# USB-C.net
KiCad netlist of a schematic drawn in Altium Designer
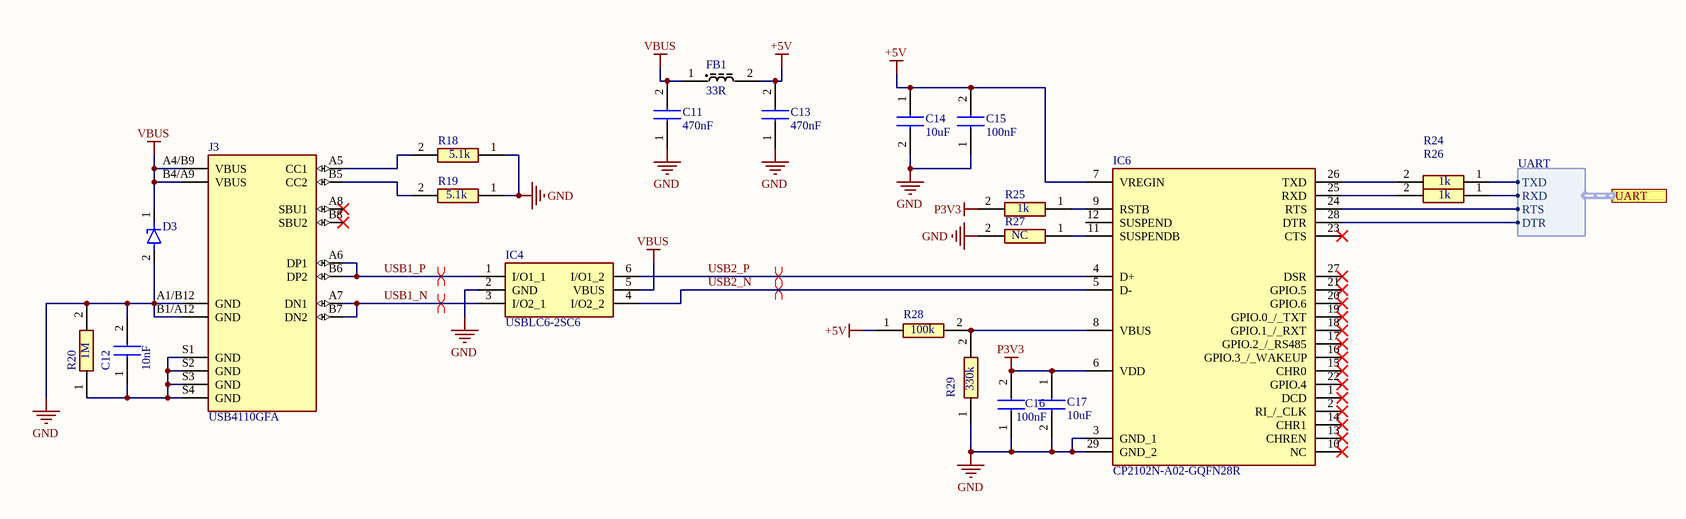
[diagram p0: USB-C.SchDoc]

(export (version "E")
  (design (tool "Eeschema 10.0.6"))
  (components
    (comp (ref "C11")
      (value "470nF")
      (footprint "SamacSys:GRM15x")
      (description "Capacitor")
      (fields
        (field (name "MANUFACTURER_PART_NUMBER") "GRM155R61H474KE11J")
        (field (name "MOUSER PART NUMBER") "81-GRM155R61H474KE1J")
      )
      (libsource (lib "*") (part "GRM155R61H474KE11J"))
    )
    (comp (ref "C12")
      (value "10nF")
      (footprint "SamacSys:GRM15x")
      (description "Capacitor")
      (fields
        (field (name "MANUFACTURER_PART_NUMBER") "GRM155R71H103KA88D")
        (field (name "MOUSER PART NUMBER") "81-GRM155R71H103KA8D")
      )
      (libsource (lib "SamacSys") (part "GRM155R71H103KA88D"))
    )
    (comp (ref "C13")
      (value "470nF")
      (footprint "SamacSys:GRM15x")
      (description "Capacitor")
      (fields
        (field (name "MANUFACTURER_PART_NUMBER") "GRM155R61H474KE11J")
        (field (name "MOUSER PART NUMBER") "81-GRM155R61H474KE1J")
      )
      (libsource (lib "*") (part "GRM155R61H474KE11J"))
    )
    (comp (ref "C14")
      (value "10uF")
      (footprint "SamacSys:GRM18x")
      (description "Capacitor")
      (fields
        (field (name "MANUFACTURER_PART_NUMBER") "GRM188R61E106KA73D")
        (field (name "MOUSER PART NUMBER") "81-GRM188R61E106KA3D")
      )
      (libsource (lib "*") (part "GRM188R61E106KA73D"))
    )
    (comp (ref "C15")
      (value "100nF")
      (footprint "SamacSys:CAPC1005X70N")
      (description "Capacitor")
      (fields
        (field (name "MANUFACTURER_PART_NUMBER") "GRM155R61A104KA01D")
        (field (name "MOUSER PART NUMBER") "81-GRM155R61A104KA01")
      )
      (libsource (lib "*") (part "GRM155R61A104KA01D"))
    )
    (comp (ref "C16")
      (value "100nF")
      (footprint "SamacSys:CAPC1005X70N")
      (description "Capacitor")
      (fields
        (field (name "MANUFACTURER_PART_NUMBER") "GRM155R61A104KA01D")
        (field (name "MOUSER PART NUMBER") "81-GRM155R61A104KA01")
      )
      (libsource (lib "*") (part "GRM155R61A104KA01D"))
    )
    (comp (ref "C17")
      (value "10uF")
      (footprint "SamacSys:GRM18x")
      (description "Capacitor")
      (fields
        (field (name "MANUFACTURER_PART_NUMBER") "GRM188R61E106KA73D")
        (field (name "MOUSER PART NUMBER") "81-GRM188R61E106KA3D")
      )
      (libsource (lib "*") (part "GRM188R61E106KA73D"))
    )
    (comp (ref "D3")
      (value "ESDA25P35-1U1M")
      (footprint "SamacSys:ESDA25P351U1M")
      (description "TVS Diode (Uni-directional)")
      (fields (field (name "MOUSER PART NUMBER") "511-ESDA25P35-1U1M"))
      (libsource (lib "SamacSys") (part "ESDA25P35-1U1M"))
    )
    (comp (ref "FB1")
      (value "33R")
      (footprint "SamacSys:BLM18SP221SN1B")
      (description "Ferrite Bead")
      (fields
        (field (name "MANUFACTURER_PART_NUMBER") "BLM18SG330SN1D")
        (field (name "MOUSER PART NUMBER") "81-BLM18SG330SN1D")
      )
      (libsource (lib "SamacSys") (part "BLM18SG330SN1D"))
    )
    (comp (ref "IC4")
      (value "USBLC6-2SC6")
      (footprint "SamacSys:SOT95P280X145-6N")
      (description "Integrated Circuit")
      (fields (field (name "MOUSER PART NUMBER") "511-USBLC6-2SC6"))
      (libsource (lib "SamacSys") (part "USBLC6-2SC6"))
    )
    (comp (ref "IC6")
      (value "CP2102N-A02-GQFN28R")
      (footprint "SamacSys:QFN50P500X500X80-29N-D")
      (description "Integrated Circuit")
      (fields (field (name "MOUSER PART NUMBER") "634-CP2102NA02QFN28R"))
      (libsource (lib "SamacSys") (part "CP2102N-A02-GQFN28R"))
    )
    (comp (ref "J3")
      (value "USB4110GFA")
      (footprint "SamacSys:GCT_USB4110GFA")
      (fields (field (name "MF") "Global Connector Technology"))
      (libsource (lib "SamacSys") (part "USB4110GFA"))
    )
    (comp (ref "R18")
      (value "5.1k")
      (footprint "SamacSys:RESC1005X35N")
      (description "Resistor")
      (fields (field (name "MANUFACTURER_PART_NUMBER") "RT0402FRE075K1L"))
      (libsource (lib "SamacSys") (part "RT0402FRE075K1L"))
    )
    (comp (ref "R19")
      (value "5.1k")
      (footprint "SamacSys:RESC1005X35N")
      (description "Resistor")
      (fields (field (name "MANUFACTURER_PART_NUMBER") "RT0402FRE075K1L"))
      (libsource (lib "SamacSys") (part "RT0402FRE075K1L"))
    )
    (comp (ref "R20")
      (value "1M")
      (footprint "SamacSys:RESC1005X40N")
      (description "Resistor")
      (fields
        (field (name "MANUFACTURER_PART_NUMBER") "RC0402FR-071ML")
        (field (name "MOUSER PART NUMBER") "603-RC0402FR-071ML")
      )
      (libsource (lib "*") (part "RC0402FR-071ML"))
    )
    (comp (ref "R24")
      (value "1k")
      (footprint "SamacSys:RESC1005X35N")
      (description "Resistor")
      (fields
        (field (name "MANUFACTURER_PART_NUMBER") "RT0402FRE071KL")
        (field (name "ARROW PART NUMBER") "RT0402FRE07100KL")
      )
      (libsource (lib "SamacSys") (part "RT0402FRE071KL"))
    )
    (comp (ref "R25")
      (value "1k")
      (footprint "SamacSys:RESC1005X35N")
      (description "Resistor")
      (fields
        (field (name "MANUFACTURER_PART_NUMBER") "RT0402FRE071KL")
        (field (name "ARROW PART NUMBER") "RT0402FRE07100KL")
      )
      (libsource (lib "SamacSys") (part "RT0402FRE071KL"))
    )
    (comp (ref "R26")
      (value "1k")
      (footprint "SamacSys:RESC1005X35N")
      (description "Resistor")
      (fields
        (field (name "MANUFACTURER_PART_NUMBER") "RT0402FRE071KL")
        (field (name "ARROW PART NUMBER") "RT0402FRE07100KL")
      )
      (libsource (lib "SamacSys") (part "RT0402FRE071KL"))
    )
    (comp (ref "R27")
      (value "NC")
      (footprint "SamacSys:RESC1005X35N")
      (description "Resistor")
      (fields
        (field (name "MANUFACTURER_PART_NUMBER") "RT0402FRE0710KL")
        (field (name "MOUSER PART NUMBER") "603-RT0402FRE0710KL")
      )
      (libsource (lib "SamacSys") (part "RT0402FRE0710KL"))
    )
    (comp (ref "R28")
      (value "100k")
      (footprint "SamacSys:RESC1005X40N")
      (description "Resistor")
      (fields (field (name "MANUFACTURER_PART_NUMBER") "RC0402BR-07100KL"))
      (libsource (lib "SamacSys") (part "RC0402BR-07100KL"))
    )
    (comp (ref "R29")
      (value "330k")
      (footprint "SamacSys:RESC1005X40N")
      (description "Resistor")
      (fields (field (name "MANUFACTURER_PART_NUMBER") "RC0402BR-07330KL"))
      (libsource (lib "SamacSys") (part "RC0402BR-07330KL"))
    )
  )
  (nets
    (net (code "2") (name "+5V") (class "Default")
      (node (ref "C13") (pin "2") (pinfunction "2_2") (pintype "passive"))
      (node (ref "C14") (pin "1") (pinfunction "1_1") (pintype "passive"))
      (node (ref "C15") (pin "2") (pinfunction "2_2") (pintype "passive"))
      (node (ref "FB1") (pin "2") (pinfunction "2_2") (pintype "passive"))
      (node (ref "IC6") (pin "7") (pinfunction "VREGIN_7") (pintype "passive"))
      (node (ref "R28") (pin "1") (pinfunction "1_1") (pintype "passive"))
    )
    (net (code "3") (name "/DTR") (class "Default")
      (node (ref "IC6") (pin "28") (pinfunction "DTR_28") (pintype "passive"))
    )
    (net (code "4") (name "/RTS") (class "Default")
      (node (ref "IC6") (pin "24") (pinfunction "RTS_24") (pintype "passive"))
    )
    (net (code "5") (name "/RXD") (class "Default")
      (node (ref "R26") (pin "1") (pinfunction "1_1") (pintype "passive"))
    )
    (net (code "6") (name "/TXD") (class "Default")
      (node (ref "R24") (pin "1") (pinfunction "1_1") (pintype "passive"))
    )
    (net (code "7") (name "/USB1_N") (class "Default")
      (node (ref "IC4") (pin "3") (pinfunction "I/O2_1_3") (pintype "passive"))
      (node (ref "J3") (pin "A7") (pinfunction "DN1_A7") (pintype "bidirectional"))
      (node (ref "J3") (pin "B7") (pinfunction "DN2_B7") (pintype "bidirectional"))
    )
    (net (code "8") (name "/USB1_P") (class "Default")
      (node (ref "IC4") (pin "1") (pinfunction "I/O1_1_1") (pintype "passive"))
      (node (ref "J3") (pin "A6") (pinfunction "DP1_A6") (pintype "bidirectional"))
      (node (ref "J3") (pin "B6") (pinfunction "DP2_B6") (pintype "bidirectional"))
    )
    (net (code "9") (name "/USB2_N") (class "Default")
      (node (ref "IC4") (pin "4") (pinfunction "I/O2_2_4") (pintype "passive"))
      (node (ref "IC6") (pin "5") (pinfunction "D-_5") (pintype "passive"))
    )
    (net (code "10") (name "/USB2_P") (class "Default")
      (node (ref "IC4") (pin "6") (pinfunction "I/O1_2_6") (pintype "passive"))
      (node (ref "IC6") (pin "4") (pinfunction "D+_4") (pintype "passive"))
    )
    (net (code "12") (name "GND") (class "Default")
      (node (ref "C11") (pin "1") (pinfunction "1_1") (pintype "passive"))
      (node (ref "C12") (pin "2") (pinfunction "2_2") (pintype "passive"))
      (node (ref "C13") (pin "1") (pinfunction "1_1") (pintype "passive"))
      (node (ref "C14") (pin "2") (pinfunction "2_2") (pintype "passive"))
      (node (ref "C15") (pin "1") (pinfunction "1_1") (pintype "passive"))
      (node (ref "C16") (pin "1") (pinfunction "1_1") (pintype "passive"))
      (node (ref "C17") (pin "2") (pinfunction "2_2") (pintype "passive"))
      (node (ref "D3") (pin "2") (pinfunction "A_2") (pintype "passive"))
      (node (ref "IC4") (pin "2") (pinfunction "GND_2") (pintype "passive"))
      (node (ref "IC6") (pin "29") (pinfunction "GND_2_29") (pintype "passive"))
      (node (ref "IC6") (pin "3") (pinfunction "GND_1_3") (pintype "passive"))
      (node (ref "J3") (pin "A1/B12") (pinfunction "GND_A1/B12") (pintype "power_in"))
      (node (ref "J3") (pin "B1/A12") (pinfunction "GND_B1/A12") (pintype "power_in"))
      (node (ref "R18") (pin "1") (pinfunction "1_1") (pintype "passive"))
      (node (ref "R19") (pin "1") (pinfunction "1_1") (pintype "passive"))
      (node (ref "R20") (pin "2") (pinfunction "2_2") (pintype "passive"))
      (node (ref "R27") (pin "2") (pinfunction "2_2") (pintype "passive"))
      (node (ref "R29") (pin "1") (pinfunction "1_1") (pintype "passive"))
    )
    (net (code "13") (name "Net-(C12-Pad1)") (class "Default")
      (node (ref "C12") (pin "1") (pinfunction "1_1") (pintype "passive"))
      (node (ref "J3") (pin "S1") (pinfunction "GND_S1") (pintype "power_in"))
      (node (ref "J3") (pin "S2") (pinfunction "GND_S2") (pintype "power_in"))
      (node (ref "J3") (pin "S3") (pinfunction "GND_S3") (pintype "power_in"))
      (node (ref "J3") (pin "S4") (pinfunction "GND_S4") (pintype "power_in"))
      (node (ref "R20") (pin "1") (pinfunction "1_1") (pintype "passive"))
    )
    (net (code "14") (name "Net-(IC6-RSTB)") (class "Default")
      (node (ref "IC6") (pin "9") (pinfunction "RSTB_9") (pintype "passive"))
      (node (ref "R25") (pin "1") (pinfunction "1_1") (pintype "passive"))
    )
    (net (code "15") (name "Net-(IC6-RXD)") (class "Default")
      (node (ref "IC6") (pin "25") (pinfunction "RXD_25") (pintype "passive"))
      (node (ref "R26") (pin "2") (pinfunction "2_2") (pintype "passive"))
    )
    (net (code "16") (name "Net-(IC6-SUSPENDB)") (class "Default")
      (node (ref "IC6") (pin "11") (pinfunction "SUSPENDB_11") (pintype "passive"))
      (node (ref "R27") (pin "1") (pinfunction "1_1") (pintype "passive"))
    )
    (net (code "17") (name "Net-(IC6-TXD)") (class "Default")
      (node (ref "IC6") (pin "26") (pinfunction "TXD_26") (pintype "passive"))
      (node (ref "R24") (pin "2") (pinfunction "2_2") (pintype "passive"))
    )
    (net (code "18") (name "Net-(IC6-VBUS)") (class "Default")
      (node (ref "IC6") (pin "8") (pinfunction "VBUS_8") (pintype "passive"))
      (node (ref "R28") (pin "2") (pinfunction "2_2") (pintype "passive"))
      (node (ref "R29") (pin "2") (pinfunction "2_2") (pintype "passive"))
    )
    (net (code "19") (name "Net-(J3-CC1)") (class "Default")
      (node (ref "J3") (pin "A5") (pinfunction "CC1_A5") (pintype "bidirectional"))
      (node (ref "R18") (pin "2") (pinfunction "2_2") (pintype "passive"))
    )
    (net (code "20") (name "Net-(J3-CC2)") (class "Default")
      (node (ref "J3") (pin "B5") (pinfunction "CC2_B5") (pintype "bidirectional"))
      (node (ref "R19") (pin "2") (pinfunction "2_2") (pintype "passive"))
    )
    (net (code "21") (name "P3V3") (class "Default")
      (node (ref "C16") (pin "2") (pinfunction "2_2") (pintype "passive"))
      (node (ref "C17") (pin "1") (pinfunction "1_1") (pintype "passive"))
      (node (ref "IC6") (pin "6") (pinfunction "VDD_6") (pintype "passive"))
      (node (ref "R25") (pin "2") (pinfunction "2_2") (pintype "passive"))
    )
    (net (code "22") (name "VBUS") (class "Default")
      (node (ref "C11") (pin "2") (pinfunction "2_2") (pintype "passive"))
      (node (ref "D3") (pin "1") (pinfunction "K_1") (pintype "passive"))
      (node (ref "FB1") (pin "1") (pinfunction "1_1") (pintype "passive"))
      (node (ref "IC4") (pin "5") (pinfunction "VBUS_5") (pintype "passive"))
      (node (ref "J3") (pin "A4/B9") (pinfunction "VBUS_A4/B9") (pintype "power_in"))
      (node (ref "J3") (pin "B4/A9") (pinfunction "VBUS_B4/A9") (pintype "power_in"))
    )
    (net (code "23") (name "unconnected-(IC6-CHR0-Pad15)") (class "Default")
      (node (ref "IC6") (pin "15") (pinfunction "CHR0_15") (pintype "passive+no_connect"))
    )
    (net (code "24") (name "unconnected-(IC6-CHR1-Pad14)") (class "Default")
      (node (ref "IC6") (pin "14") (pinfunction "CHR1_14") (pintype "passive+no_connect"))
    )
    (net (code "25") (name "unconnected-(IC6-CHREN-Pad13)") (class "Default")
      (node (ref "IC6") (pin "13") (pinfunction "CHREN_13") (pintype "passive+no_connect"))
    )
    (net (code "26") (name "unconnected-(IC6-CTS-Pad23)") (class "Default")
      (node (ref "IC6") (pin "23") (pinfunction "CTS_23") (pintype "passive+no_connect"))
    )
    (net (code "27") (name "unconnected-(IC6-DCD-Pad1)") (class "Default")
      (node (ref "IC6") (pin "1") (pinfunction "DCD_1") (pintype "passive+no_connect"))
    )
    (net (code "28") (name "unconnected-(IC6-DSR-Pad27)") (class "Default")
      (node (ref "IC6") (pin "27") (pinfunction "DSR_27") (pintype "passive+no_connect"))
    )
    (net (code "29") (name "unconnected-(IC6-GPIO.0_{slash}_TXT-Pad19)") (class "Default")
      (node (ref "IC6") (pin "19") (pinfunction "GPIO.0_/_TXT_19") (pintype "passive+no_connect"))
    )
    (net (code "30") (name "unconnected-(IC6-GPIO.1_{slash}_RXT-Pad18)") (class "Default")
      (node (ref "IC6") (pin "18") (pinfunction "GPIO.1_/_RXT_18") (pintype "passive+no_connect"))
    )
    (net (code "31") (name "unconnected-(IC6-GPIO.2_{slash}_RS485-Pad17)") (class "Default")
      (node (ref "IC6") (pin "17") (pinfunction "GPIO.2_/_RS485_17") (pintype "passive+no_connect"))
    )
    (net (code "32") (name "unconnected-(IC6-GPIO.3_{slash}_WAKEUP-Pad16)") (class "Default")
      (node (ref "IC6") (pin "16") (pinfunction "GPIO.3_/_WAKEUP_16") (pintype "passive+no_connect"))
    )
    (net (code "33") (name "unconnected-(IC6-GPIO.4-Pad22)") (class "Default")
      (node (ref "IC6") (pin "22") (pinfunction "GPIO.4_22") (pintype "passive+no_connect"))
    )
    (net (code "34") (name "unconnected-(IC6-GPIO.5-Pad21)") (class "Default")
      (node (ref "IC6") (pin "21") (pinfunction "GPIO.5_21") (pintype "passive+no_connect"))
    )
    (net (code "35") (name "unconnected-(IC6-GPIO.6-Pad20)") (class "Default")
      (node (ref "IC6") (pin "20") (pinfunction "GPIO.6_20") (pintype "passive+no_connect"))
    )
    (net (code "36") (name "unconnected-(IC6-NC-Pad10)") (class "Default")
      (node (ref "IC6") (pin "10") (pinfunction "NC_10") (pintype "passive+no_connect"))
    )
    (net (code "37") (name "unconnected-(IC6-RI_{slash}_CLK-Pad2)") (class "Default")
      (node (ref "IC6") (pin "2") (pinfunction "RI_/_CLK_2") (pintype "passive+no_connect"))
    )
    (net (code "38") (name "unconnected-(IC6-SUSPEND-Pad12)") (class "Default")
      (node (ref "IC6") (pin "12") (pinfunction "SUSPEND_12") (pintype "passive"))
    )
    (net (code "39") (name "unconnected-(J3-SBU1-PadA8)") (class "Default")
      (node (ref "J3") (pin "A8") (pinfunction "SBU1_A8") (pintype "bidirectional+no_connect"))
    )
    (net (code "40") (name "unconnected-(J3-SBU2-PadB8)") (class "Default")
      (node (ref "J3") (pin "B8") (pinfunction "SBU2_B8") (pintype "bidirectional+no_connect"))
    )
  )
)
